# ControladorPID.net
KiCad netlist of a schematic drawn in EAGLE
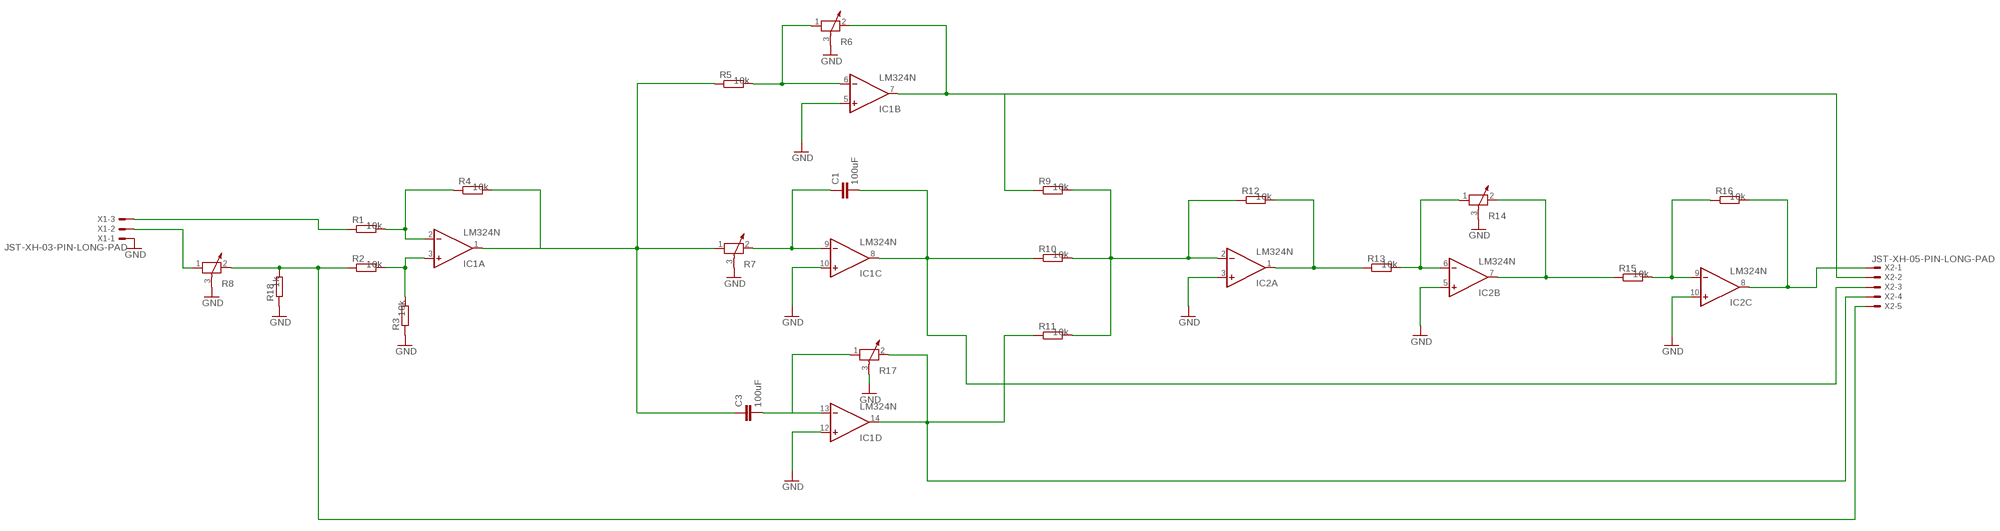
[diagram p0: schematic, sheet 1]

(export (version "E")
  (design (tool "Eeschema 10.0.6"))
  (components
    (comp (ref "C1")
      (value "100uF")
      (footprint "eagle-import:C2.5-3")
      (libsource (lib "eagle-import") (part "C2,5-3"))
    )
    (comp (ref "C3")
      (value "100uF")
      (footprint "eagle-import:C2.5-3")
      (libsource (lib "eagle-import") (part "C2,5-3"))
    )
    (comp (ref "IC1")
      (value "LM324N")
      (footprint "eagle-import:DIL14")
      (libsource (lib "eagle-import") (part "LM324N"))
    )
    (comp (ref "IC2")
      (value "LM324N")
      (footprint "eagle-import:DIL14")
      (libsource (lib "eagle-import") (part "LM324N"))
    )
    (comp (ref "R1")
      (value "R-EU_M1206")
      (footprint "eagle-import:M1206")
      (fields (field (name "SPICEPREFIX") "R") (field (name "SPICEPREFIX_1") "10k"))
      (libsource (lib "eagle-import") (part "R-EU_M1206"))
    )
    (comp (ref "R2")
      (value "R-EU_M1206")
      (footprint "eagle-import:M1206")
      (fields (field (name "SPICEPREFIX") "R") (field (name "SPICEPREFIX_1") "10k"))
      (libsource (lib "eagle-import") (part "R-EU_M1206"))
    )
    (comp (ref "R3")
      (value "R-EU_M1206")
      (footprint "eagle-import:M1206")
      (fields (field (name "SPICEPREFIX") "R") (field (name "SPICEPREFIX_1") "10k"))
      (libsource (lib "eagle-import") (part "R-EU_M1206"))
    )
    (comp (ref "R4")
      (value "R-EU_M1206")
      (footprint "eagle-import:M1206")
      (fields (field (name "SPICEPREFIX") "R") (field (name "SPICEPREFIX_1") "10k"))
      (libsource (lib "eagle-import") (part "R-EU_M1206"))
    )
    (comp (ref "R5")
      (value "R-EU_M1206")
      (footprint "eagle-import:M1206")
      (fields (field (name "SPICEPREFIX") "R") (field (name "SPICEPREFIX_1") "10k"))
      (libsource (lib "eagle-import") (part "R-EU_M1206"))
    )
    (comp (ref "R6")
      (value "POTENTIOMETER_PT-10")
      (footprint "eagle-import:PT-10")
      (libsource (lib "eagle-import") (part "POTENTIOMETER_PT-10"))
    )
    (comp (ref "R7")
      (value "POTENTIOMETER_PT-10")
      (footprint "eagle-import:PT-10")
      (libsource (lib "eagle-import") (part "POTENTIOMETER_PT-10"))
    )
    (comp (ref "R8")
      (value "POTENTIOMETER_PT-10")
      (footprint "eagle-import:PT-10")
      (libsource (lib "eagle-import") (part "POTENTIOMETER_PT-10"))
    )
    (comp (ref "R9")
      (value "R-EU_M1206")
      (footprint "eagle-import:M1206")
      (fields (field (name "SPICEPREFIX") "R") (field (name "SPICEPREFIX_1") "10k"))
      (libsource (lib "eagle-import") (part "R-EU_M1206"))
    )
    (comp (ref "R10")
      (value "R-EU_M1206")
      (footprint "eagle-import:M1206")
      (fields (field (name "SPICEPREFIX") "R") (field (name "SPICEPREFIX_1") "10k"))
      (libsource (lib "eagle-import") (part "R-EU_M1206"))
    )
    (comp (ref "R11")
      (value "R-EU_M1206")
      (footprint "eagle-import:M1206")
      (fields (field (name "SPICEPREFIX") "R") (field (name "SPICEPREFIX_1") "10k"))
      (libsource (lib "eagle-import") (part "R-EU_M1206"))
    )
    (comp (ref "R12")
      (value "R-EU_M1206")
      (footprint "eagle-import:M1206")
      (fields (field (name "SPICEPREFIX") "R") (field (name "SPICEPREFIX_1") "10k"))
      (libsource (lib "eagle-import") (part "R-EU_M1206"))
    )
    (comp (ref "R13")
      (value "R-EU_M1206")
      (footprint "eagle-import:M1206")
      (fields (field (name "SPICEPREFIX") "R") (field (name "SPICEPREFIX_1") "10k"))
      (libsource (lib "eagle-import") (part "R-EU_M1206"))
    )
    (comp (ref "R14")
      (value "POTENTIOMETER_PT-10")
      (footprint "eagle-import:PT-10")
      (libsource (lib "eagle-import") (part "POTENTIOMETER_PT-10"))
    )
    (comp (ref "R15")
      (value "R-EU_M1206")
      (footprint "eagle-import:M1206")
      (fields (field (name "SPICEPREFIX") "R") (field (name "SPICEPREFIX_1") "10k"))
      (libsource (lib "eagle-import") (part "R-EU_M1206"))
    )
    (comp (ref "R16")
      (value "R-EU_M1206")
      (footprint "eagle-import:M1206")
      (fields (field (name "SPICEPREFIX") "R") (field (name "SPICEPREFIX_1") "10k"))
      (libsource (lib "eagle-import") (part "R-EU_M1206"))
    )
    (comp (ref "R17")
      (value "POTENTIOMETER_PT-10")
      (footprint "eagle-import:PT-10")
      (libsource (lib "eagle-import") (part "POTENTIOMETER_PT-10"))
    )
    (comp (ref "R18")
      (value "R-EU_M1206")
      (footprint "eagle-import:M1206")
      (fields (field (name "SPICEPREFIX") "R") (field (name "SPICEPREFIX_1") "1k"))
      (libsource (lib "eagle-import") (part "R-EU_M1206"))
    )
    (comp (ref "X1")
      (value "JST-XH-03-PIN-LONG-PAD")
      (footprint "eagle-import:JST-XH-03-PACKAGE-LONG-PAD")
      (libsource (lib "eagle-import") (part "JST-XH-03-PIN-LONG-PAD"))
    )
    (comp (ref "X2")
      (value "JST-XH-05-PIN-LONG-PAD")
      (footprint "eagle-import:JST-XH-05-PACKAGE-LONG-PAD")
      (libsource (lib "eagle-import") (part "JST-XH-05-PIN-LONG-PAD"))
    )
  )
  (nets
    (net (code "1") (name "GND") (class "Default")
      (node (ref "IC1") (pin "10") (pinfunction "+IN_10") (pintype "input"))
      (node (ref "IC1") (pin "12") (pinfunction "+IN_12") (pintype "input"))
      (node (ref "IC1") (pin "5") (pinfunction "+IN_5") (pintype "input"))
      (node (ref "IC2") (pin "10") (pinfunction "+IN_10") (pintype "input"))
      (node (ref "IC2") (pin "3") (pinfunction "+IN_3") (pintype "input"))
      (node (ref "IC2") (pin "5") (pinfunction "+IN_5") (pintype "input"))
      (node (ref "R14") (pin "3") (pinfunction "3_3") (pintype "passive"))
      (node (ref "R17") (pin "3") (pinfunction "3_3") (pintype "passive"))
      (node (ref "R18") (pin "1") (pinfunction "1_1") (pintype "passive"))
      (node (ref "R3") (pin "1") (pinfunction "1_1") (pintype "passive"))
      (node (ref "R6") (pin "3") (pinfunction "3_3") (pintype "passive"))
      (node (ref "R7") (pin "3") (pinfunction "3_3") (pintype "passive"))
      (node (ref "R8") (pin "3") (pinfunction "3_3") (pintype "passive"))
      (node (ref "X1") (pin "1") (pinfunction "S_1") (pintype "passive"))
    )
    (net (code "2") (name "Net-(IC1A-+IN)") (class "Default")
      (node (ref "IC1") (pin "3") (pinfunction "+IN_3") (pintype "input"))
      (node (ref "R2") (pin "2") (pinfunction "2_2") (pintype "passive"))
      (node (ref "R3") (pin "2") (pinfunction "2_2") (pintype "passive"))
    )
    (net (code "3") (name "Net-(IC1A--IN)") (class "Default")
      (node (ref "IC1") (pin "2") (pinfunction "-IN_2") (pintype "input"))
      (node (ref "R1") (pin "2") (pinfunction "2_2") (pintype "passive"))
      (node (ref "R4") (pin "1") (pinfunction "1_1") (pintype "passive"))
    )
    (net (code "4") (name "Net-(IC1A-OUT)") (class "Default")
      (node (ref "C3") (pin "1") (pinfunction "1_1") (pintype "passive"))
      (node (ref "IC1") (pin "1") (pinfunction "OUT_1") (pintype "output"))
      (node (ref "R4") (pin "2") (pinfunction "2_2") (pintype "passive"))
      (node (ref "R5") (pin "1") (pinfunction "1_1") (pintype "passive"))
      (node (ref "R7") (pin "1") (pinfunction "1_1") (pintype "passive"))
    )
    (net (code "5") (name "Net-(IC1B--IN)") (class "Default")
      (node (ref "IC1") (pin "6") (pinfunction "-IN_6") (pintype "input"))
      (node (ref "R5") (pin "2") (pinfunction "2_2") (pintype "passive"))
      (node (ref "R6") (pin "1") (pinfunction "1_1") (pintype "passive"))
    )
    (net (code "6") (name "Net-(IC1B-OUT)") (class "Default")
      (node (ref "IC1") (pin "7") (pinfunction "OUT_7") (pintype "output"))
      (node (ref "R6") (pin "2") (pinfunction "2_2") (pintype "passive"))
      (node (ref "R9") (pin "1") (pinfunction "1_1") (pintype "passive"))
      (node (ref "X2") (pin "2") (pinfunction "S_2") (pintype "passive"))
    )
    (net (code "7") (name "Net-(IC1C--IN)") (class "Default")
      (node (ref "C1") (pin "1") (pinfunction "1_1") (pintype "passive"))
      (node (ref "IC1") (pin "9") (pinfunction "-IN_9") (pintype "input"))
      (node (ref "R7") (pin "2") (pinfunction "2_2") (pintype "passive"))
    )
    (net (code "8") (name "Net-(IC1C-OUT)") (class "Default")
      (node (ref "C1") (pin "2") (pinfunction "2_2") (pintype "passive"))
      (node (ref "IC1") (pin "8") (pinfunction "OUT_8") (pintype "output"))
      (node (ref "R10") (pin "1") (pinfunction "1_1") (pintype "passive"))
      (node (ref "X2") (pin "3") (pinfunction "S_3") (pintype "passive"))
    )
    (net (code "9") (name "Net-(IC1D--IN)") (class "Default")
      (node (ref "C3") (pin "2") (pinfunction "2_2") (pintype "passive"))
      (node (ref "IC1") (pin "13") (pinfunction "-IN_13") (pintype "input"))
    )
    (net (code "10") (name "Net-(IC1D-OUT)") (class "Default")
      (node (ref "IC1") (pin "14") (pinfunction "OUT_14") (pintype "output"))
      (node (ref "R11") (pin "1") (pinfunction "1_1") (pintype "passive"))
      (node (ref "R17") (pin "2") (pinfunction "2_2") (pintype "passive"))
      (node (ref "X2") (pin "4") (pinfunction "S_4") (pintype "passive"))
    )
    (net (code "11") (name "Net-(IC2A--IN)") (class "Default")
      (node (ref "IC2") (pin "2") (pinfunction "-IN_2") (pintype "input"))
      (node (ref "R10") (pin "2") (pinfunction "2_2") (pintype "passive"))
      (node (ref "R11") (pin "2") (pinfunction "2_2") (pintype "passive"))
      (node (ref "R12") (pin "1") (pinfunction "1_1") (pintype "passive"))
      (node (ref "R9") (pin "2") (pinfunction "2_2") (pintype "passive"))
    )
    (net (code "12") (name "Net-(IC2A-OUT)") (class "Default")
      (node (ref "IC2") (pin "1") (pinfunction "OUT_1") (pintype "output"))
      (node (ref "R12") (pin "2") (pinfunction "2_2") (pintype "passive"))
      (node (ref "R13") (pin "1") (pinfunction "1_1") (pintype "passive"))
    )
    (net (code "13") (name "Net-(IC2B--IN)") (class "Default")
      (node (ref "IC2") (pin "6") (pinfunction "-IN_6") (pintype "input"))
      (node (ref "R13") (pin "2") (pinfunction "2_2") (pintype "passive"))
      (node (ref "R14") (pin "1") (pinfunction "1_1") (pintype "passive"))
    )
    (net (code "14") (name "Net-(IC2B-OUT)") (class "Default")
      (node (ref "IC2") (pin "7") (pinfunction "OUT_7") (pintype "output"))
      (node (ref "R14") (pin "2") (pinfunction "2_2") (pintype "passive"))
      (node (ref "R15") (pin "1") (pinfunction "1_1") (pintype "passive"))
    )
    (net (code "15") (name "Net-(IC2C--IN)") (class "Default")
      (node (ref "IC2") (pin "9") (pinfunction "-IN_9") (pintype "input"))
      (node (ref "R15") (pin "2") (pinfunction "2_2") (pintype "passive"))
      (node (ref "R16") (pin "1") (pinfunction "1_1") (pintype "passive"))
    )
    (net (code "16") (name "Net-(IC2C-OUT)") (class "Default")
      (node (ref "IC2") (pin "8") (pinfunction "OUT_8") (pintype "output"))
      (node (ref "R16") (pin "2") (pinfunction "2_2") (pintype "passive"))
      (node (ref "X2") (pin "1") (pinfunction "S_1") (pintype "passive"))
    )
    (net (code "17") (name "Net-(X1B-S)") (class "Default")
      (node (ref "R8") (pin "1") (pinfunction "1_1") (pintype "passive"))
      (node (ref "X1") (pin "2") (pinfunction "S_2") (pintype "passive"))
    )
    (net (code "18") (name "Net-(X1C-S)") (class "Default")
      (node (ref "R1") (pin "1") (pinfunction "1_1") (pintype "passive"))
      (node (ref "X1") (pin "3") (pinfunction "S_3") (pintype "passive"))
    )
    (net (code "19") (name "Net-(X2E-S)") (class "Default")
      (node (ref "R18") (pin "2") (pinfunction "2_2") (pintype "passive"))
      (node (ref "R2") (pin "1") (pinfunction "1_1") (pintype "passive"))
      (node (ref "R8") (pin "2") (pinfunction "2_2") (pintype "passive"))
      (node (ref "X2") (pin "5") (pinfunction "S_5") (pintype "passive"))
    )
    (net (code "20") (name "unconnected-(R17-Pad1)") (class "Default")
      (node (ref "R17") (pin "1") (pinfunction "1_1") (pintype "passive"))
    )
  )
)
